# ac-dc_brd_2014-10-19.net
KiCad netlist of a schematic drawn in EAGLE
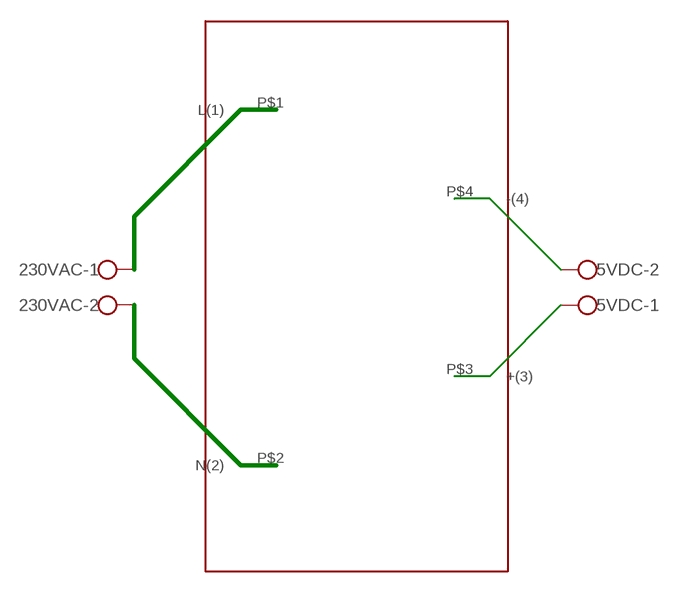
[diagram p0: schematic, sheet 1]

(export (version "E")
  (design (tool "Eeschema 10.0.6"))
  (components
    (comp (ref "5VDC")
      (value "W237-102")
      (footprint "eagle-import:W237-102")
      (fields (field (name "MPN") "237-102"))
      (libsource (lib "eagle-import") (part "W237-102"))
    )
    (comp (ref "230VAC")
      (value "W237-102")
      (footprint "eagle-import:W237-102")
      (fields (field (name "MPN") "237-102"))
      (libsource (lib "eagle-import") (part "W237-102"))
    )
    (comp (ref "U$2")
      (value "VTX_214")
      (footprint "eagle-import:VTX-214-005")
      (libsource (lib "eagle-import") (part "VTX_214"))
    )
  )
  (nets
    (net (code "1") (name "Net-(5VDCA-KL)") (class "Default")
      (node (ref "5VDC") (pin "1") (pinfunction "KL_1") (pintype "passive"))
      (node (ref "U$2") (pin "P$3") (pinfunction "+(3)_P$3") (pintype "output"))
    )
    (net (code "2") (name "Net-(5VDCB-KL)") (class "Default")
      (node (ref "5VDC") (pin "2") (pinfunction "KL_2") (pintype "passive"))
      (node (ref "U$2") (pin "P$4") (pinfunction "-(4)_P$4") (pintype "output"))
    )
    (net (code "3") (name "Net-(230VACA-KL)") (class "Default")
      (node (ref "230VAC") (pin "1") (pinfunction "KL_1") (pintype "passive"))
      (node (ref "U$2") (pin "P$1") (pinfunction "L(1)_P$1") (pintype "input"))
    )
    (net (code "4") (name "Net-(230VACB-KL)") (class "Default")
      (node (ref "230VAC") (pin "2") (pinfunction "KL_2") (pintype "passive"))
      (node (ref "U$2") (pin "P$2") (pinfunction "N(2)_P$2") (pintype "input"))
    )
  )
)
